# dr-who.net
KiCad netlist of a schematic drawn in EAGLE
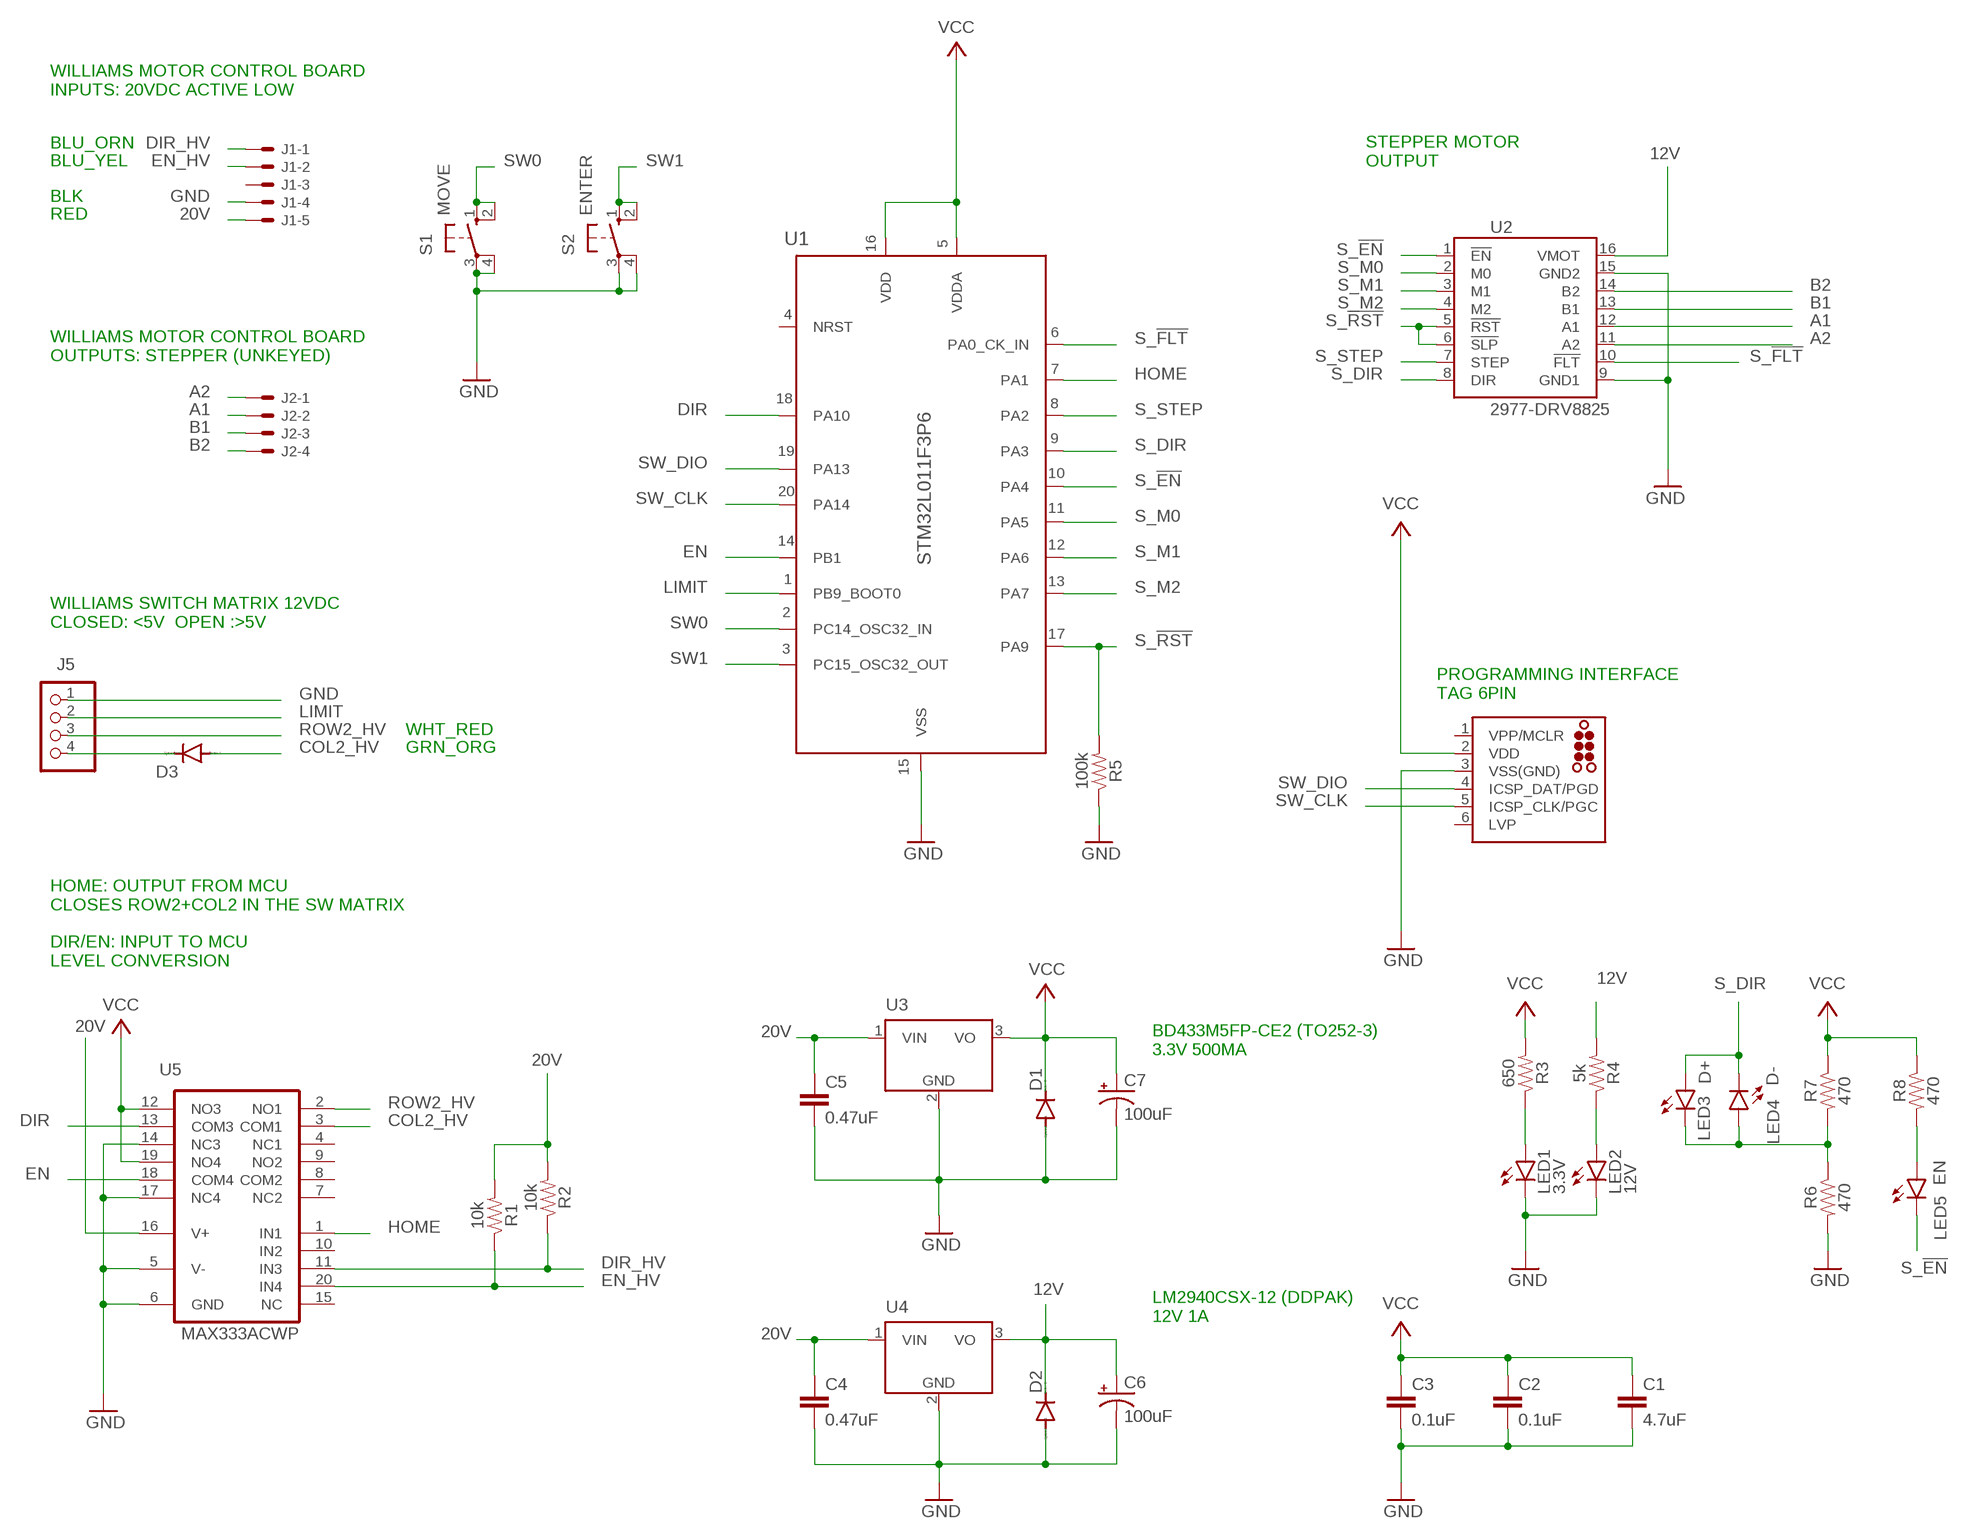
[diagram p0: schematic, sheet 1]

(export (version "E")
  (design (tool "Eeschema 10.0.6"))
  (components
    (comp (ref "C1")
      (value "4.7uF")
      (footprint "eagle-import:0603")
      (libsource (lib "eagle-import") (part "4.7UF0603"))
    )
    (comp (ref "C2")
      (value "0.1uF")
      (footprint "eagle-import:0603")
      (libsource (lib "eagle-import") (part "0.1UF-0603-25V-(+80/-20%)"))
    )
    (comp (ref "C3")
      (value "0.1uF")
      (footprint "eagle-import:0603")
      (libsource (lib "eagle-import") (part "0.1UF-0603-25V-(+80/-20%)"))
    )
    (comp (ref "C4")
      (value "0.47uF")
      (footprint "eagle-import:0603")
      (libsource (lib "eagle-import") (part "470PF-0603-50V-5%"))
    )
    (comp (ref "C5")
      (value "0.47uF")
      (footprint "eagle-import:0603")
      (libsource (lib "eagle-import") (part "470PF-0603-50V-5%"))
    )
    (comp (ref "C6")
      (value "100uF")
      (footprint "eagle-import:CPOL-RADIAL-2.5MM-6.5MM")
      (libsource (lib "eagle-import") (part "100UF-POLAR-RADIAL-2.5MM-25V-20%"))
    )
    (comp (ref "C7")
      (value "100uF")
      (footprint "eagle-import:CPOL-RADIAL-2.5MM-6.5MM")
      (libsource (lib "eagle-import") (part "100UF-POLAR-RADIAL-2.5MM-25V-20%"))
    )
    (comp (ref "D1")
      (value "DIODE-SOD323-R")
      (footprint "eagle-import:SOD323-R")
      (libsource (lib "eagle-import") (part "DIODE-SOD323-R"))
    )
    (comp (ref "D2")
      (value "DIODE-SOD323-R")
      (footprint "eagle-import:SOD323-R")
      (libsource (lib "eagle-import") (part "DIODE-SOD323-R"))
    )
    (comp (ref "D3")
      (value "DIODE-SOD323-R")
      (footprint "eagle-import:SOD323-R")
      (libsource (lib "eagle-import") (part "DIODE-SOD323-R"))
    )
    (comp (ref "J1")
      (value "KK-156-5")
      (footprint "eagle-import:KK-156-5")
      (fields (field (name "MF") "MOLEX"))
      (libsource (lib "eagle-import") (part "KK-156-5"))
    )
    (comp (ref "J2")
      (value "KK-156-4")
      (footprint "eagle-import:KK-156-4")
      (fields (field (name "MF") "MOLEX"))
      (libsource (lib "eagle-import") (part "KK-156-4"))
    )
    (comp (ref "J4")
      (value "TC2030-MCP-NL")
      (footprint "eagle-import:TC2030-MCP-NL")
      (libsource (lib "eagle-import") (part "TC2030-MCP-NL"))
    )
    (comp (ref "J5")
      (value "PINHD-1X4")
      (footprint "eagle-import:1X04")
      (libsource (lib "eagle-import") (part "PINHD-1X4"))
    )
    (comp (ref "LED1")
      (value "3.3V")
      (footprint "eagle-import:LED3MM")
      (libsource (lib "eagle-import") (part "LED3MM"))
    )
    (comp (ref "LED2")
      (value "12V")
      (footprint "eagle-import:LED3MM")
      (libsource (lib "eagle-import") (part "LED3MM"))
    )
    (comp (ref "LED3")
      (value "D+")
      (footprint "eagle-import:LED3MM")
      (libsource (lib "eagle-import") (part "LED3MM"))
    )
    (comp (ref "LED4")
      (value "D-")
      (footprint "eagle-import:LED3MM")
      (libsource (lib "eagle-import") (part "LED3MM"))
    )
    (comp (ref "LED5")
      (value "EN")
      (footprint "eagle-import:LED3MM")
      (libsource (lib "eagle-import") (part "LED3MM"))
    )
    (comp (ref "R1")
      (value "10k")
      (footprint "eagle-import:0603")
      (libsource (lib "eagle-import") (part "10KOHM-0603-1/10W-1%"))
    )
    (comp (ref "R2")
      (value "10k")
      (footprint "eagle-import:0603")
      (libsource (lib "eagle-import") (part "10KOHM-0603-1/10W-1%"))
    )
    (comp (ref "R3")
      (value "650")
      (footprint "eagle-import:0603")
      (libsource (lib "eagle-import") (part "10KOHM-0603-1/10W-1%"))
    )
    (comp (ref "R4")
      (value "5k")
      (footprint "eagle-import:0603")
      (libsource (lib "eagle-import") (part "10KOHM-0603-1/10W-1%"))
    )
    (comp (ref "R5")
      (value "100k")
      (footprint "eagle-import:0603")
      (libsource (lib "eagle-import") (part "10KOHM-0603-1/10W-1%"))
    )
    (comp (ref "R6")
      (value "470")
      (footprint "eagle-import:0603")
      (libsource (lib "eagle-import") (part "10KOHM-0603-1/10W-1%"))
    )
    (comp (ref "R7")
      (value "470")
      (footprint "eagle-import:0603")
      (libsource (lib "eagle-import") (part "10KOHM-0603-1/10W-1%"))
    )
    (comp (ref "R8")
      (value "470")
      (footprint "eagle-import:0603")
      (libsource (lib "eagle-import") (part "10KOHM-0603-1/10W-1%"))
    )
    (comp (ref "S1")
      (value "MOVE")
      (footprint "eagle-import:B3F_40XX")
      (libsource (lib "eagle-import") (part "40/XX"))
    )
    (comp (ref "S2")
      (value "ENTER")
      (footprint "eagle-import:B3F_40XX")
      (libsource (lib "eagle-import") (part "40/XX"))
    )
    (comp (ref "U1")
      (value "STM32L011F3P6")
      (footprint "eagle-import:TSSOP20-I")
      (libsource (lib "eagle-import") (part "STM32L011F3P6"))
    )
    (comp (ref "U2")
      (value "2977-DRV8825")
      (footprint "eagle-import:DRV8825")
      (libsource (lib "eagle-import") (part "2977-DRV8825"))
    )
    (comp (ref "U3")
      (value "LM2936DT-3.3")
      (footprint "eagle-import:TO252")
      (fields (field (name "MPN") "LM2936DT-3.3.") (field (name "MPN_1") "BD433M5FP-CE2"))
      (libsource (lib "eagle-import") (part "national-semiconductor_307_LM2936?DT-3.3"))
    )
    (comp (ref "U4")
      (value "LM2936D2PAK")
      (footprint "eagle-import:D2PAK")
      (libsource (lib "eagle-import") (part "LM2936?D2PAK"))
    )
    (comp (ref "U5")
      (value "MAX333ACWP")
      (footprint "eagle-import:SO20L")
      (fields (field (name "MF") "MAXIM") (field (name "MPN") "MAX333ACWP+"))
      (libsource (lib "eagle-import") (part "MAX333ACWP"))
    )
  )
  (nets
    (net (code "1") (name "/12V") (class "Default")
      (node (ref "C6") (pin "1") (pinfunction "+_1") (pintype "passive"))
      (node (ref "D2") (pin "C") (pinfunction "C_C") (pintype "passive"))
      (node (ref "R4") (pin "2") (pinfunction "2_2") (pintype "passive"))
      (node (ref "U2") (pin "16") (pinfunction "VMOT_16") (pintype "power_in"))
      (node (ref "U4") (pin "3") (pinfunction "VO_3") (pintype "passive"))
    )
    (net (code "2") (name "/20V") (class "Default")
      (node (ref "C4") (pin "1") (pinfunction "1_1") (pintype "passive"))
      (node (ref "C5") (pin "1") (pinfunction "1_1") (pintype "passive"))
      (node (ref "J1") (pin "5") (pinfunction "S_5") (pintype "passive"))
      (node (ref "R1") (pin "2") (pinfunction "2_2") (pintype "passive"))
      (node (ref "R2") (pin "2") (pinfunction "2_2") (pintype "passive"))
      (node (ref "U3") (pin "1") (pinfunction "VIN_1") (pintype "input"))
      (node (ref "U4") (pin "1") (pinfunction "VIN_1") (pintype "input"))
      (node (ref "U5") (pin "16") (pinfunction "V+_16") (pintype "power_in"))
    )
    (net (code "3") (name "/A1") (class "Default")
      (node (ref "J2") (pin "2") (pinfunction "S_2") (pintype "passive"))
      (node (ref "U2") (pin "12") (pinfunction "A1_12") (pintype "output"))
    )
    (net (code "4") (name "/A2") (class "Default")
      (node (ref "J2") (pin "1") (pinfunction "S_1") (pintype "passive"))
      (node (ref "U2") (pin "11") (pinfunction "A2_11") (pintype "output"))
    )
    (net (code "5") (name "/B1") (class "Default")
      (node (ref "J2") (pin "3") (pinfunction "S_3") (pintype "passive"))
      (node (ref "U2") (pin "13") (pinfunction "B1_13") (pintype "output"))
    )
    (net (code "6") (name "/B2") (class "Default")
      (node (ref "J2") (pin "4") (pinfunction "S_4") (pintype "passive"))
      (node (ref "U2") (pin "14") (pinfunction "B2_14") (pintype "output"))
    )
    (net (code "7") (name "/COL2_HV") (class "Default")
      (node (ref "D3") (pin "A") (pinfunction "A_A") (pintype "passive"))
      (node (ref "U5") (pin "3") (pinfunction "COM1_3") (pintype "passive"))
    )
    (net (code "8") (name "/DIR") (class "Default")
      (node (ref "U1") (pin "18") (pinfunction "PA10_18") (pintype "passive"))
      (node (ref "U5") (pin "13") (pinfunction "COM3_13") (pintype "passive"))
    )
    (net (code "9") (name "/DIR_HV") (class "Default")
      (node (ref "J1") (pin "1") (pinfunction "S_1") (pintype "passive"))
      (node (ref "R2") (pin "1") (pinfunction "1_1") (pintype "passive"))
      (node (ref "U5") (pin "11") (pinfunction "IN3_11") (pintype "input"))
    )
    (net (code "10") (name "/EN") (class "Default")
      (node (ref "U1") (pin "14") (pinfunction "PB1_14") (pintype "passive"))
      (node (ref "U5") (pin "18") (pinfunction "COM4_18") (pintype "passive"))
    )
    (net (code "11") (name "/EN_HV") (class "Default")
      (node (ref "J1") (pin "2") (pinfunction "S_2") (pintype "passive"))
      (node (ref "R1") (pin "1") (pinfunction "1_1") (pintype "passive"))
      (node (ref "U5") (pin "20") (pinfunction "IN4_20") (pintype "input"))
    )
    (net (code "12") (name "/HOME") (class "Default")
      (node (ref "U1") (pin "7") (pinfunction "PA1_7") (pintype "passive"))
      (node (ref "U5") (pin "1") (pinfunction "IN1_1") (pintype "input"))
    )
    (net (code "13") (name "/LIMIT") (class "Default")
      (node (ref "J5") (pin "2") (pinfunction "2_2") (pintype "passive"))
      (node (ref "U1") (pin "1") (pinfunction "PB9_BOOT0_1") (pintype "passive"))
    )
    (net (code "14") (name "/ROW2_HV") (class "Default")
      (node (ref "J5") (pin "3") (pinfunction "3_3") (pintype "passive"))
      (node (ref "U5") (pin "2") (pinfunction "NO1_2") (pintype "passive"))
    )
    (net (code "15") (name "/SW0") (class "Default")
      (node (ref "S1") (pin "1") (pinfunction "S_1") (pintype "passive"))
      (node (ref "S1") (pin "2") (pinfunction "S1_2") (pintype "passive"))
      (node (ref "U1") (pin "2") (pinfunction "PC14_OSC32_IN_2") (pintype "passive"))
    )
    (net (code "16") (name "/SW1") (class "Default")
      (node (ref "S2") (pin "1") (pinfunction "S_1") (pintype "passive"))
      (node (ref "S2") (pin "2") (pinfunction "S1_2") (pintype "passive"))
      (node (ref "U1") (pin "3") (pinfunction "PC15_OSC32_OUT_3") (pintype "passive"))
    )
    (net (code "17") (name "/SW_CLK") (class "Default")
      (node (ref "J4") (pin "5") (pinfunction "ICSP_CLK/PGC_5") (pintype "output"))
      (node (ref "U1") (pin "20") (pinfunction "PA14_20") (pintype "passive"))
    )
    (net (code "18") (name "/SW_DIO") (class "Default")
      (node (ref "J4") (pin "4") (pinfunction "ICSP_DAT/PGD_4") (pintype "bidirectional"))
      (node (ref "U1") (pin "19") (pinfunction "PA13_19") (pintype "passive"))
    )
    (net (code "19") (name "/S_DIR") (class "Default")
      (node (ref "LED3") (pin "A") (pinfunction "A_A") (pintype "passive"))
      (node (ref "LED4") (pin "K") (pinfunction "C_K") (pintype "passive"))
      (node (ref "U1") (pin "9") (pinfunction "PA3_9") (pintype "passive"))
      (node (ref "U2") (pin "8") (pinfunction "DIR_8") (pintype "input"))
    )
    (net (code "20") (name "/S_M0") (class "Default")
      (node (ref "U1") (pin "11") (pinfunction "PA5_11") (pintype "passive"))
      (node (ref "U2") (pin "2") (pinfunction "M0_2") (pintype "passive"))
    )
    (net (code "21") (name "/S_M1") (class "Default")
      (node (ref "U1") (pin "12") (pinfunction "PA6_12") (pintype "passive"))
      (node (ref "U2") (pin "3") (pinfunction "M1_3") (pintype "passive"))
    )
    (net (code "22") (name "/S_M2") (class "Default")
      (node (ref "U1") (pin "13") (pinfunction "PA7_13") (pintype "passive"))
      (node (ref "U2") (pin "4") (pinfunction "M2_4") (pintype "passive"))
    )
    (net (code "23") (name "/S_STEP") (class "Default")
      (node (ref "U1") (pin "8") (pinfunction "PA2_8") (pintype "passive"))
      (node (ref "U2") (pin "7") (pinfunction "STEP_7") (pintype "input"))
    )
    (net (code "24") (name "/S_~{EN}") (class "Default")
      (node (ref "LED5") (pin "K") (pinfunction "C_K") (pintype "passive"))
      (node (ref "U1") (pin "10") (pinfunction "PA4_10") (pintype "passive"))
      (node (ref "U2") (pin "1") (pinfunction "~{EN}_1") (pintype "passive"))
    )
    (net (code "25") (name "/S_~{FLT}") (class "Default")
      (node (ref "U1") (pin "6") (pinfunction "PA0_CK_IN_6") (pintype "passive"))
      (node (ref "U2") (pin "10") (pinfunction "~{FLT}_10") (pintype "open_collector"))
    )
    (net (code "26") (name "/S_~{RST}") (class "Default")
      (node (ref "R5") (pin "2") (pinfunction "2_2") (pintype "passive"))
      (node (ref "U1") (pin "17") (pinfunction "PA9_17") (pintype "passive"))
      (node (ref "U2") (pin "5") (pinfunction "~{RST}_5") (pintype "input"))
      (node (ref "U2") (pin "6") (pinfunction "~{SLP}_6") (pintype "input"))
    )
    (net (code "27") (name "GND") (class "Default")
      (node (ref "C1") (pin "2") (pinfunction "2_2") (pintype "passive"))
      (node (ref "C2") (pin "2") (pinfunction "2_2") (pintype "passive"))
      (node (ref "C3") (pin "2") (pinfunction "2_2") (pintype "passive"))
      (node (ref "C4") (pin "2") (pinfunction "2_2") (pintype "passive"))
      (node (ref "C5") (pin "2") (pinfunction "2_2") (pintype "passive"))
      (node (ref "C6") (pin "2") (pinfunction "-_2") (pintype "passive"))
      (node (ref "C7") (pin "2") (pinfunction "-_2") (pintype "passive"))
      (node (ref "D1") (pin "A") (pinfunction "A_A") (pintype "passive"))
      (node (ref "D2") (pin "A") (pinfunction "A_A") (pintype "passive"))
      (node (ref "J1") (pin "4") (pinfunction "S_4") (pintype "passive"))
      (node (ref "J4") (pin "3") (pinfunction "VSS(GND)_3") (pintype "power_in"))
      (node (ref "J5") (pin "1") (pinfunction "1_1") (pintype "passive"))
      (node (ref "LED1") (pin "K") (pinfunction "C_K") (pintype "passive"))
      (node (ref "LED2") (pin "K") (pinfunction "C_K") (pintype "passive"))
      (node (ref "R5") (pin "1") (pinfunction "1_1") (pintype "passive"))
      (node (ref "R6") (pin "2") (pinfunction "2_2") (pintype "passive"))
      (node (ref "S1") (pin "3") (pinfunction "P_3") (pintype "passive"))
      (node (ref "S1") (pin "4") (pinfunction "P1_4") (pintype "passive"))
      (node (ref "S2") (pin "3") (pinfunction "P_3") (pintype "passive"))
      (node (ref "S2") (pin "4") (pinfunction "P1_4") (pintype "passive"))
      (node (ref "U1") (pin "15") (pinfunction "VSS_15") (pintype "passive"))
      (node (ref "U2") (pin "15") (pinfunction "GND2_15") (pintype "power_in"))
      (node (ref "U2") (pin "9") (pinfunction "GND1_9") (pintype "power_in"))
      (node (ref "U3") (pin "2") (pinfunction "GND_2") (pintype "passive"))
      (node (ref "U4") (pin "2") (pinfunction "GND_2") (pintype "passive"))
      (node (ref "U5") (pin "14") (pinfunction "NC3_14") (pintype "passive"))
      (node (ref "U5") (pin "17") (pinfunction "NC4_17") (pintype "passive"))
      (node (ref "U5") (pin "5") (pinfunction "V-_5") (pintype "power_in"))
      (node (ref "U5") (pin "6") (pinfunction "GND_6") (pintype "power_in"))
    )
    (net (code "28") (name "Net-(D3-PadC)") (class "Default")
      (node (ref "D3") (pin "C") (pinfunction "C_C") (pintype "passive"))
      (node (ref "J5") (pin "4") (pinfunction "4_4") (pintype "passive"))
    )
    (net (code "29") (name "Net-(LED1-PadA)") (class "Default")
      (node (ref "LED1") (pin "A") (pinfunction "A_A") (pintype "passive"))
      (node (ref "R3") (pin "1") (pinfunction "1_1") (pintype "passive"))
    )
    (net (code "30") (name "Net-(LED2-PadA)") (class "Default")
      (node (ref "LED2") (pin "A") (pinfunction "A_A") (pintype "passive"))
      (node (ref "R4") (pin "1") (pinfunction "1_1") (pintype "passive"))
    )
    (net (code "31") (name "Net-(LED3-C)") (class "Default")
      (node (ref "LED3") (pin "K") (pinfunction "C_K") (pintype "passive"))
      (node (ref "LED4") (pin "A") (pinfunction "A_A") (pintype "passive"))
      (node (ref "R6") (pin "1") (pinfunction "1_1") (pintype "passive"))
      (node (ref "R7") (pin "2") (pinfunction "2_2") (pintype "passive"))
    )
    (net (code "32") (name "Net-(LED5-PadA)") (class "Default")
      (node (ref "LED5") (pin "A") (pinfunction "A_A") (pintype "passive"))
      (node (ref "R8") (pin "2") (pinfunction "2_2") (pintype "passive"))
    )
    (net (code "33") (name "VCC") (class "Default")
      (node (ref "C1") (pin "1") (pinfunction "1_1") (pintype "passive"))
      (node (ref "C2") (pin "1") (pinfunction "1_1") (pintype "passive"))
      (node (ref "C3") (pin "1") (pinfunction "1_1") (pintype "passive"))
      (node (ref "C7") (pin "1") (pinfunction "+_1") (pintype "passive"))
      (node (ref "D1") (pin "C") (pinfunction "C_C") (pintype "passive"))
      (node (ref "J4") (pin "2") (pinfunction "VDD_2") (pintype "power_in"))
      (node (ref "R3") (pin "2") (pinfunction "2_2") (pintype "passive"))
      (node (ref "R7") (pin "1") (pinfunction "1_1") (pintype "passive"))
      (node (ref "R8") (pin "1") (pinfunction "1_1") (pintype "passive"))
      (node (ref "U1") (pin "16") (pinfunction "VDD_16") (pintype "passive"))
      (node (ref "U1") (pin "5") (pinfunction "VDDA_5") (pintype "passive"))
      (node (ref "U3") (pin "3") (pinfunction "VO_3") (pintype "passive"))
      (node (ref "U5") (pin "12") (pinfunction "NO3_12") (pintype "passive"))
      (node (ref "U5") (pin "19") (pinfunction "NO4_19") (pintype "passive"))
    )
    (net (code "34") (name "unconnected-(J1C-S-Pad3)") (class "Default")
      (node (ref "J1") (pin "3") (pinfunction "S_3") (pintype "passive"))
    )
    (net (code "35") (name "unconnected-(J4-LVP-Pad6)") (class "Default")
      (node (ref "J4") (pin "6") (pinfunction "LVP_6") (pintype "bidirectional"))
    )
    (net (code "36") (name "unconnected-(J4-VPP{slash}MCLR-Pad1)") (class "Default")
      (node (ref "J4") (pin "1") (pinfunction "VPP/MCLR_1") (pintype "passive"))
    )
    (net (code "37") (name "unconnected-(U1-NRST-Pad4)") (class "Default")
      (node (ref "U1") (pin "4") (pinfunction "NRST_4") (pintype "passive"))
    )
    (net (code "38") (name "unconnected-(U5-COM2-Pad8)") (class "Default")
      (node (ref "U5") (pin "8") (pinfunction "COM2_8") (pintype "passive"))
    )
    (net (code "39") (name "unconnected-(U5-IN2-Pad10)") (class "Default")
      (node (ref "U5") (pin "10") (pinfunction "IN2_10") (pintype "input"))
    )
    (net (code "40") (name "unconnected-(U5-NC-Pad15)") (class "Default")
      (node (ref "U5") (pin "15") (pinfunction "NC_15") (pintype "no_connect"))
    )
    (net (code "41") (name "unconnected-(U5-NC1-Pad4)") (class "Default")
      (node (ref "U5") (pin "4") (pinfunction "NC1_4") (pintype "passive"))
    )
    (net (code "42") (name "unconnected-(U5-NC2-Pad7)") (class "Default")
      (node (ref "U5") (pin "7") (pinfunction "NC2_7") (pintype "passive"))
    )
    (net (code "43") (name "unconnected-(U5-NO2-Pad9)") (class "Default")
      (node (ref "U5") (pin "9") (pinfunction "NO2_9") (pintype "passive"))
    )
  )
)
